# display_spi7.net
KiCad netlist of a schematic drawn in EAGLE
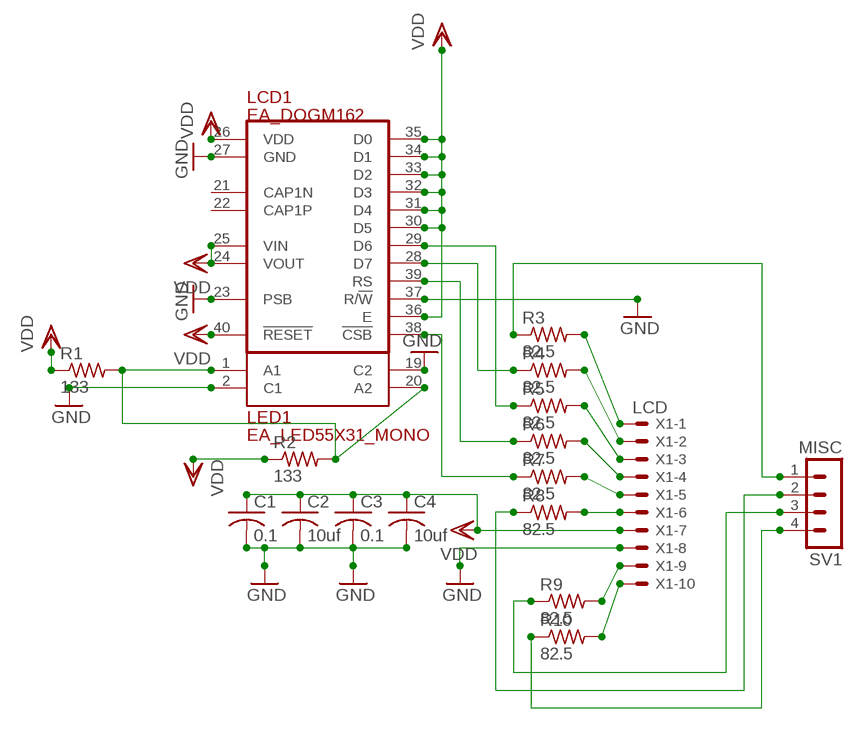
[diagram p0: schematic, sheet 1]

(export (version "E")
  (design (tool "Eeschema 10.0.6"))
  (components
    (comp (ref "C1")
      (value "0.1")
      (footprint "eagle-import:C1206")
      (libsource (lib "eagle-import") (part "C-USC1206"))
    )
    (comp (ref "C2")
      (value "10uf")
      (footprint "eagle-import:C1206")
      (libsource (lib "eagle-import") (part "C-USC1206"))
    )
    (comp (ref "C3")
      (value "0.1")
      (footprint "eagle-import:C1206")
      (libsource (lib "eagle-import") (part "C-USC1206"))
    )
    (comp (ref "C4")
      (value "10uf")
      (footprint "eagle-import:C1206")
      (libsource (lib "eagle-import") (part "C-USC1206"))
    )
    (comp (ref "LCD1")
      (value "EA_DOGM162")
      (footprint "eagle-import:EA_DOGM")
      (libsource (lib "eagle-import") (part "EA_DOGM162"))
    )
    (comp (ref "LED1")
      (value "EA_LED55X31_MONO")
      (footprint "eagle-import:EA_LED55X31")
      (libsource (lib "eagle-import") (part "EA_LED55X31_MONO"))
    )
    (comp (ref "R1")
      (value "133")
      (footprint "eagle-import:R1206")
      (libsource (lib "eagle-import") (part "R-US_R1206"))
    )
    (comp (ref "R2")
      (value "133")
      (footprint "eagle-import:R1206")
      (libsource (lib "eagle-import") (part "R-US_R1206"))
    )
    (comp (ref "R3")
      (value "82.5")
      (footprint "eagle-import:R1206")
      (libsource (lib "eagle-import") (part "R-US_R1206"))
    )
    (comp (ref "R4")
      (value "82.5")
      (footprint "eagle-import:R1206")
      (libsource (lib "eagle-import") (part "R-US_R1206"))
    )
    (comp (ref "R5")
      (value "82.5")
      (footprint "eagle-import:R1206")
      (libsource (lib "eagle-import") (part "R-US_R1206"))
    )
    (comp (ref "R6")
      (value "82.5")
      (footprint "eagle-import:R1206")
      (libsource (lib "eagle-import") (part "R-US_R1206"))
    )
    (comp (ref "R7")
      (value "82.5")
      (footprint "eagle-import:R1206")
      (libsource (lib "eagle-import") (part "R-US_R1206"))
    )
    (comp (ref "R8")
      (value "82.5")
      (footprint "eagle-import:R1206")
      (libsource (lib "eagle-import") (part "R-US_R1206"))
    )
    (comp (ref "R9")
      (value "82.5")
      (footprint "eagle-import:R1206")
      (libsource (lib "eagle-import") (part "R-US_R1206"))
    )
    (comp (ref "R10")
      (value "82.5")
      (footprint "eagle-import:R1206")
      (libsource (lib "eagle-import") (part "R-US_R1206"))
    )
    (comp (ref "SV1")
      (value "MISC")
      (footprint "eagle-import:MA04-1")
      (libsource (lib "eagle-import") (part "MA04-1"))
    )
    (comp (ref "X1")
      (value "LCD")
      (footprint "eagle-import:22-23-2101")
      (fields (field (name "MF") "MOLEX") (field (name "MPN") "22-23-2101"))
      (libsource (lib "eagle-import") (part "22-23-2101"))
    )
  )
  (nets
    (net (code "1") (name "GND") (class "Default")
      (node (ref "C1") (pin "2") (pinfunction "2_2") (pintype "passive"))
      (node (ref "C2") (pin "2") (pinfunction "2_2") (pintype "passive"))
      (node (ref "C3") (pin "2") (pinfunction "2_2") (pintype "passive"))
      (node (ref "C4") (pin "2") (pinfunction "2_2") (pintype "passive"))
      (node (ref "LCD1") (pin "23") (pinfunction "PSB_23") (pintype "input"))
      (node (ref "LCD1") (pin "27") (pinfunction "GND_27") (pintype "power_in"))
      (node (ref "LCD1") (pin "37") (pinfunction "R/~{W}_37") (pintype "input"))
      (node (ref "LED1") (pin "19") (pinfunction "C2_19") (pintype "passive"))
      (node (ref "LED1") (pin "2") (pinfunction "C1_2") (pintype "passive"))
      (node (ref "X1") (pin "8") (pinfunction "S_8") (pintype "passive"))
    )
    (net (code "2") (name "Net-(LCD1-D6)") (class "Default")
      (node (ref "LCD1") (pin "29") (pinfunction "D6_29") (pintype "bidirectional"))
      (node (ref "R5") (pin "1") (pinfunction "1_1") (pintype "passive"))
    )
    (net (code "3") (name "Net-(LCD1-D7)") (class "Default")
      (node (ref "LCD1") (pin "28") (pinfunction "D7_28") (pintype "bidirectional"))
      (node (ref "R4") (pin "1") (pinfunction "1_1") (pintype "passive"))
    )
    (net (code "4") (name "Net-(LCD1-RS)") (class "Default")
      (node (ref "LCD1") (pin "39") (pinfunction "RS_39") (pintype "input"))
      (node (ref "R6") (pin "1") (pinfunction "1_1") (pintype "passive"))
    )
    (net (code "5") (name "Net-(LCD1-~{CSB})") (class "Default")
      (node (ref "LCD1") (pin "38") (pinfunction "~{CSB}_38") (pintype "input"))
      (node (ref "R7") (pin "1") (pinfunction "1_1") (pintype "passive"))
    )
    (net (code "6") (name "Net-(LED1-A1)") (class "Default")
      (node (ref "LED1") (pin "1") (pinfunction "A1_1") (pintype "passive"))
      (node (ref "LED1") (pin "20") (pinfunction "A2_20") (pintype "passive"))
      (node (ref "R1") (pin "2") (pinfunction "2_2") (pintype "passive"))
      (node (ref "R2") (pin "2") (pinfunction "2_2") (pintype "passive"))
    )
    (net (code "7") (name "Net-(R3-Pad1)") (class "Default")
      (node (ref "R3") (pin "1") (pinfunction "1_1") (pintype "passive"))
      (node (ref "SV1") (pin "1") (pinfunction "1_1") (pintype "passive"))
    )
    (net (code "8") (name "Net-(R8-Pad1)") (class "Default")
      (node (ref "R8") (pin "1") (pinfunction "1_1") (pintype "passive"))
      (node (ref "SV1") (pin "2") (pinfunction "2_2") (pintype "passive"))
    )
    (net (code "9") (name "Net-(R9-Pad1)") (class "Default")
      (node (ref "R9") (pin "1") (pinfunction "1_1") (pintype "passive"))
      (node (ref "SV1") (pin "3") (pinfunction "3_3") (pintype "passive"))
    )
    (net (code "10") (name "Net-(R10-Pad1)") (class "Default")
      (node (ref "R10") (pin "1") (pinfunction "1_1") (pintype "passive"))
      (node (ref "SV1") (pin "4") (pinfunction "4_4") (pintype "passive"))
    )
    (net (code "11") (name "Net-(X1A-S)") (class "Default")
      (node (ref "R3") (pin "2") (pinfunction "2_2") (pintype "passive"))
      (node (ref "X1") (pin "1") (pinfunction "S_1") (pintype "passive"))
    )
    (net (code "12") (name "Net-(X1B-S)") (class "Default")
      (node (ref "R10") (pin "2") (pinfunction "2_2") (pintype "passive"))
      (node (ref "X1") (pin "10") (pinfunction "S_10") (pintype "passive"))
    )
    (net (code "13") (name "Net-(X1C-S)") (class "Default")
      (node (ref "R4") (pin "2") (pinfunction "2_2") (pintype "passive"))
      (node (ref "X1") (pin "2") (pinfunction "S_2") (pintype "passive"))
    )
    (net (code "14") (name "Net-(X1D-S)") (class "Default")
      (node (ref "R5") (pin "2") (pinfunction "2_2") (pintype "passive"))
      (node (ref "X1") (pin "3") (pinfunction "S_3") (pintype "passive"))
    )
    (net (code "15") (name "Net-(X1E-S)") (class "Default")
      (node (ref "R6") (pin "2") (pinfunction "2_2") (pintype "passive"))
      (node (ref "X1") (pin "4") (pinfunction "S_4") (pintype "passive"))
    )
    (net (code "16") (name "Net-(X1F-S)") (class "Default")
      (node (ref "R7") (pin "2") (pinfunction "2_2") (pintype "passive"))
      (node (ref "X1") (pin "5") (pinfunction "S_5") (pintype "passive"))
    )
    (net (code "17") (name "Net-(X1G-S)") (class "Default")
      (node (ref "R8") (pin "2") (pinfunction "2_2") (pintype "passive"))
      (node (ref "X1") (pin "6") (pinfunction "S_6") (pintype "passive"))
    )
    (net (code "18") (name "Net-(X1J-S)") (class "Default")
      (node (ref "R9") (pin "2") (pinfunction "2_2") (pintype "passive"))
      (node (ref "X1") (pin "9") (pinfunction "S_9") (pintype "passive"))
    )
    (net (code "19") (name "VDD") (class "Default")
      (node (ref "C1") (pin "1") (pinfunction "1_1") (pintype "passive"))
      (node (ref "C2") (pin "1") (pinfunction "1_1") (pintype "passive"))
      (node (ref "C3") (pin "1") (pinfunction "1_1") (pintype "passive"))
      (node (ref "C4") (pin "1") (pinfunction "1_1") (pintype "passive"))
      (node (ref "LCD1") (pin "24") (pinfunction "VOUT_24") (pintype "passive"))
      (node (ref "LCD1") (pin "25") (pinfunction "VIN_25") (pintype "passive"))
      (node (ref "LCD1") (pin "26") (pinfunction "VDD_26") (pintype "power_in"))
      (node (ref "LCD1") (pin "30") (pinfunction "D5_30") (pintype "bidirectional"))
      (node (ref "LCD1") (pin "31") (pinfunction "D4_31") (pintype "bidirectional"))
      (node (ref "LCD1") (pin "32") (pinfunction "D3_32") (pintype "bidirectional"))
      (node (ref "LCD1") (pin "33") (pinfunction "D2_33") (pintype "bidirectional"))
      (node (ref "LCD1") (pin "34") (pinfunction "D1_34") (pintype "bidirectional"))
      (node (ref "LCD1") (pin "35") (pinfunction "D0_35") (pintype "bidirectional"))
      (node (ref "LCD1") (pin "36") (pinfunction "E_36") (pintype "input"))
      (node (ref "LCD1") (pin "40") (pinfunction "~{RESET}_40") (pintype "input"))
      (node (ref "R1") (pin "1") (pinfunction "1_1") (pintype "passive"))
      (node (ref "R2") (pin "1") (pinfunction "1_1") (pintype "passive"))
      (node (ref "X1") (pin "7") (pinfunction "S_7") (pintype "passive"))
    )
    (net (code "20") (name "unconnected-(LCD1-CAP1N-Pad21)") (class "Default")
      (node (ref "LCD1") (pin "21") (pinfunction "CAP1N_21") (pintype "passive"))
    )
    (net (code "21") (name "unconnected-(LCD1-CAP1P-Pad22)") (class "Default")
      (node (ref "LCD1") (pin "22") (pinfunction "CAP1P_22") (pintype "passive"))
    )
  )
)
